# MCU.net
KiCad netlist of a schematic drawn in Altium Designer
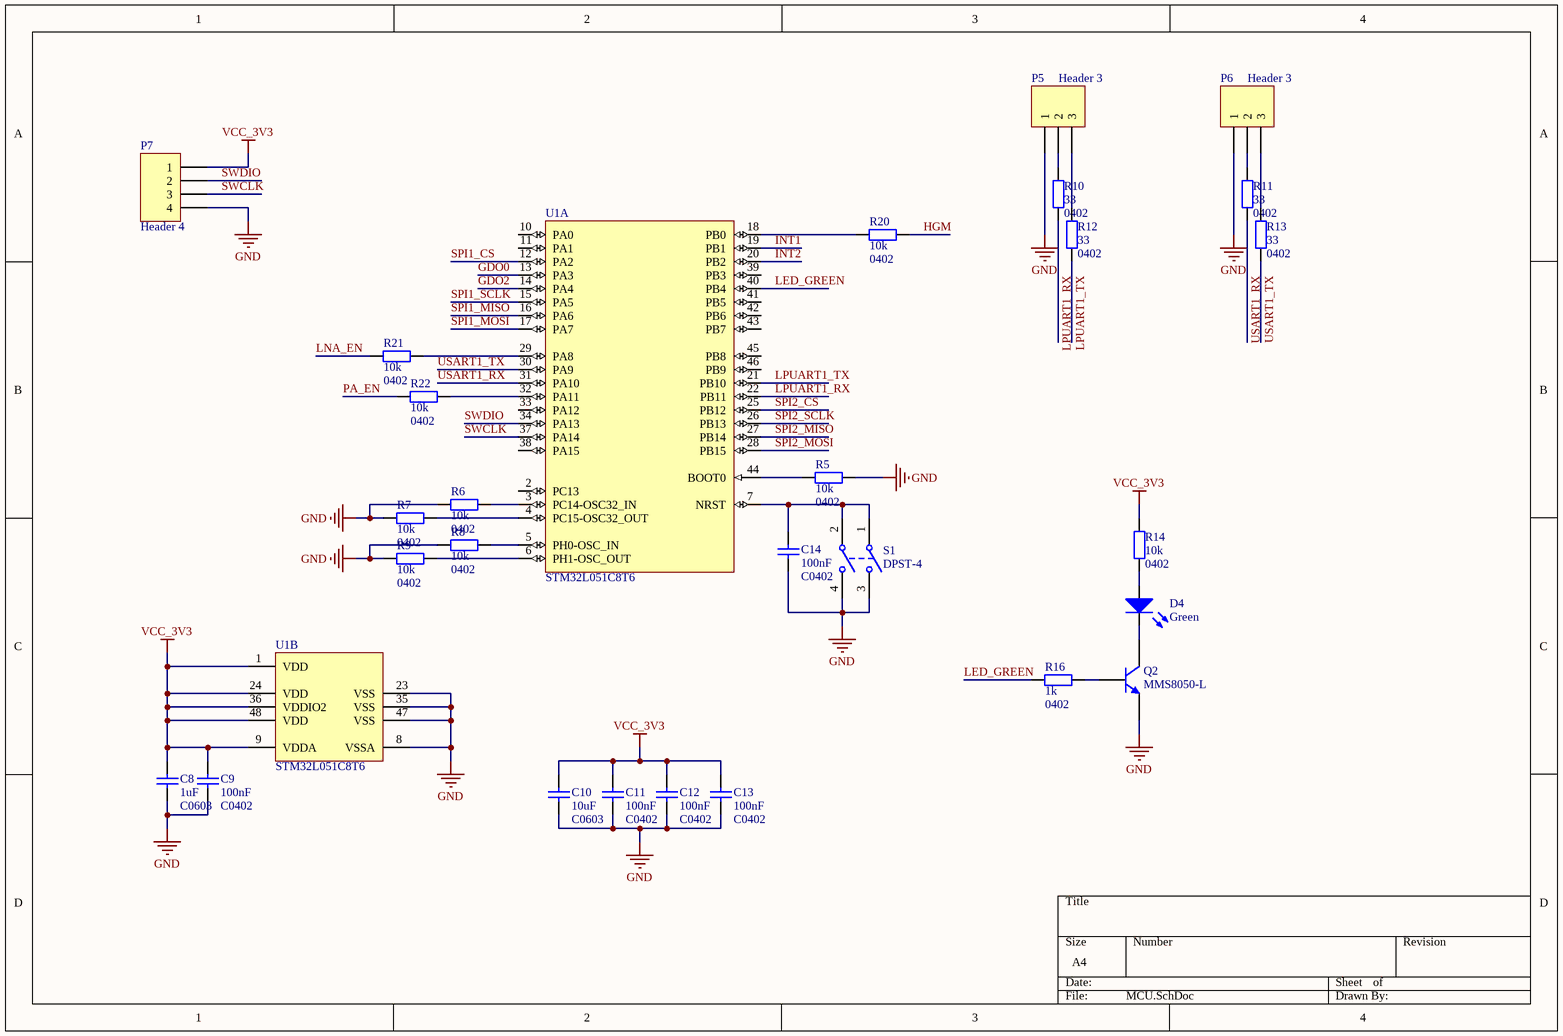
[diagram p0: MCU.SchDoc]

(export (version "E")
  (design (tool "Eeschema 10.0.6"))
  (components
    (comp (ref "C8")
      (value "1uF")
      (footprint "1608[0603]")
      (description "Capacitor (0603,X5R,1uF,DC 10V,+/-10%) TDK")
      (fields (field (name "PACKAGEREFERENCE") "C0603") (field (name "PUBLISHER") "Altium Limited"))
      (libsource (lib "RFID_CC1101PA2") (part "CGA3E2X5R1A105K080AA"))
    )
    (comp (ref "C9")
      (value "100nF")
      (footprint "0402")
      (description "Capacitor (0402,X5R,100nF,DC 10V,±10%) TDK")
      (fields (field (name "PACKAGEREFERENCE") "C0402") (field (name "PUBLISHER") "Altium Limited"))
      (libsource (lib "RFID_CC1101PA2") (part "CGA2B2X5R1A104K050BA"))
    )
    (comp (ref "C10")
      (value "10uF")
      (footprint "1608[0603]")
      (description "Capacitor (0603,X5R,10uF,DC 10V,±10%) TDK")
      (fields (field (name "PACKAGEREFERENCE") "C0603") (field (name "PUBLISHER") "Altium Limited"))
      (libsource (lib "RFID_CC1101PA2") (part "C1608X5R1A106K080AC"))
    )
    (comp (ref "C11")
      (value "100nF")
      (footprint "0402")
      (description "Capacitor (0402,X5R,100nF,DC 10V,±10%) TDK")
      (fields (field (name "PACKAGEREFERENCE") "C0402") (field (name "PUBLISHER") "Altium Limited"))
      (libsource (lib "RFID_CC1101PA2") (part "CGA2B2X5R1A104K050BA"))
    )
    (comp (ref "C12")
      (value "100nF")
      (footprint "0402")
      (description "Capacitor (0402,X5R,100nF,DC 10V,±10%) TDK")
      (fields (field (name "PACKAGEREFERENCE") "C0402") (field (name "PUBLISHER") "Altium Limited"))
      (libsource (lib "RFID_CC1101PA2") (part "CGA2B2X5R1A104K050BA"))
    )
    (comp (ref "C13")
      (value "100nF")
      (footprint "0402")
      (description "Capacitor (0402,X5R,100nF,DC 10V,±10%) TDK")
      (fields (field (name "PACKAGEREFERENCE") "C0402") (field (name "PUBLISHER") "Altium Limited"))
      (libsource (lib "RFID_CC1101PA2") (part "CGA2B2X5R1A104K050BA"))
    )
    (comp (ref "C14")
      (value "100nF")
      (footprint "0402")
      (description "Capacitor (0402,X5R,100nF,DC 10V,±10%) TDK")
      (fields (field (name "PACKAGEREFERENCE") "C0402") (field (name "PUBLISHER") "Altium Limited"))
      (libsource (lib "RFID_CC1101PA2") (part "CGA2B2X5R1A104K050BA"))
    )
    (comp (ref "D4")
      (value "Green")
      (footprint "0603/K")
      (description "Standard 0603 SMD LED, Green, 2.1V,-40 °C to +100 °C")
      (fields (field (name "PUBLISHER") "Altium Limited"))
      (libsource (lib "GPS_GPRS") (part "TLMG1100-GS08"))
    )
    (comp (ref "P5")
      (value "Header 3")
      (footprint "HDR1X3")
      (description "Header, 3-Pin")
      (fields (field (name "PUBLISHER") "Altium Limited"))
      (libsource (lib "GPS_NB") (part "Header 3"))
    )
    (comp (ref "P6")
      (value "Header 3")
      (footprint "HDR1X3")
      (description "Header, 3-Pin")
      (fields (field (name "PUBLISHER") "Altium Limited"))
      (libsource (lib "GPS_NB") (part "Header 3"))
    )
    (comp (ref "P7")
      (value "Header 4")
      (footprint "HDR1x4-2MM")
      (description "Header, 4-Pin")
      (fields (field (name "PUBLISHER") "Altium Limited"))
      (libsource (lib "TMR_Header") (part "Header 4"))
    )
    (comp (ref "Q2")
      (value "MMS8050-L")
      (footprint "SOT-23B_N")
      (description "NPN Silicon  Plastic-Encapsulate  Transistor , MCC , Range:120-200")
      (fields (field (name "PUBLISHER") "Altium Limited"))
      (libsource (lib "GPS_NB") (part "MMS8050-L"))
    )
    (comp (ref "R5")
      (value "10k")
      (footprint "RESC1005X04N")
      (description "Resistor 0402(1005) 10kΩ ±1%")
      (fields (field (name "PACKAGEREFERENCE") "0402"))
      (libsource (lib "RFID_CC1101PA2") (part "RC0402FR-0710KL"))
    )
    (comp (ref "R6")
      (value "10k")
      (footprint "RESC1005X04N")
      (description "Resistor 0402(1005) 10kΩ ±1%")
      (fields (field (name "PACKAGEREFERENCE") "0402"))
      (libsource (lib "RFID_CC1101PA2") (part "RC0402FR-0710KL"))
    )
    (comp (ref "R7")
      (value "10k")
      (footprint "RESC1005X04N")
      (description "Resistor 0402(1005) 10kΩ ±1%")
      (fields (field (name "PACKAGEREFERENCE") "0402"))
      (libsource (lib "RFID_CC1101PA2") (part "RC0402FR-0710KL"))
    )
    (comp (ref "R8")
      (value "10k")
      (footprint "RESC1005X04N")
      (description "Resistor 0402(1005) 10kΩ ±1%")
      (fields (field (name "PACKAGEREFERENCE") "0402"))
      (libsource (lib "RFID_CC1101PA2") (part "RC0402FR-0710KL"))
    )
    (comp (ref "R9")
      (value "10k")
      (footprint "RESC1005X04N")
      (description "Resistor 0402(1005) 10kΩ ±1%")
      (fields (field (name "PACKAGEREFERENCE") "0402"))
      (libsource (lib "RFID_CC1101PA2") (part "RC0402FR-0710KL"))
    )
    (comp (ref "R10")
      (value "33")
      (footprint "RESC1005X04N")
      (description "Resistor 0402(1005) 33Ω ±1%")
      (fields (field (name "PACKAGEREFERENCE") "0402"))
      (libsource (lib "GPS_NB") (part "RC0402FR-0733RL"))
    )
    (comp (ref "R11")
      (value "33")
      (footprint "RESC1005X04N")
      (description "Resistor 0402(1005) 33Ω ±1%")
      (fields (field (name "PACKAGEREFERENCE") "0402"))
      (libsource (lib "GPS_NB") (part "RC0402FR-0733RL"))
    )
    (comp (ref "R12")
      (value "33")
      (footprint "RESC1005X04N")
      (description "Resistor 0402(1005) 33Ω ±1%")
      (fields (field (name "PACKAGEREFERENCE") "0402"))
      (libsource (lib "") (part "RC0402FR-0733RL_1"))
    )
    (comp (ref "R13")
      (value "33")
      (footprint "RESC1005X04N")
      (description "Resistor 0402(1005) 33Ω ±1%")
      (fields (field (name "PACKAGEREFERENCE") "0402"))
      (libsource (lib "") (part "RC0402FR-0733RL_1"))
    )
    (comp (ref "R14")
      (value "10k")
      (footprint "RESC1005X04N")
      (description "Resistor 0402(1005) 10kΩ ±1%")
      (fields (field (name "PACKAGEREFERENCE") "0402"))
      (libsource (lib "GPS_NB") (part "RC0402FR-0710KL"))
    )
    (comp (ref "R16")
      (value "1k")
      (footprint "RESC1005X04N")
      (description "Resistor 0402(1005) 1kΩ ±1%")
      (fields (field (name "PACKAGEREFERENCE") "0402"))
      (libsource (lib "GPS_NB") (part "RC0402FR-071KL"))
    )
    (comp (ref "R20")
      (value "10k")
      (footprint "RESC1005X04N")
      (description "Resistor 0402(1005) 10kΩ ±1%")
      (fields (field (name "PACKAGEREFERENCE") "0402"))
      (libsource (lib "RFID_CC1101_869MHz") (part "RC0402FR-0710KL"))
    )
    (comp (ref "R21")
      (value "10k")
      (footprint "RESC1005X04N")
      (description "Resistor 0402(1005) 10kΩ ±1%")
      (fields (field (name "PACKAGEREFERENCE") "0402"))
      (libsource (lib "RFID_CC1101_869MHz") (part "RC0402FR-0710KL"))
    )
    (comp (ref "R22")
      (value "10k")
      (footprint "RESC1005X04N")
      (description "Resistor 0402(1005) 10kΩ ±1%")
      (fields (field (name "PACKAGEREFERENCE") "0402"))
      (libsource (lib "RFID_CC1101_869MHz") (part "RC0402FR-0710KL"))
    )
    (comp (ref "S1")
      (value "DPST-4")
      (footprint "DPST")
      (description "5.2*5.2轻触开关")
      (fields (field (name "PUBLISHER") "Altium Limited"))
      (libsource (lib "RFID_CC1101PA2") (part "CX-G001"))
    )
    (comp (ref "U1")
      (value "STM32L051C8T6")
      (footprint "STM-LQFP48_N")
      (libsource (lib "RFID_CC1101PA2") (part "STM32L051C8T6"))
    )
  )
  (nets
    (net (code "1") (name "/GDO0") (class "Default")
      (node (ref "U1") (pin "13") (pinfunction "PA3_13") (pintype "bidirectional"))
    )
    (net (code "2") (name "/GDO2") (class "Default")
      (node (ref "U1") (pin "14") (pinfunction "PA4_14") (pintype "bidirectional"))
    )
    (net (code "3") (name "/HGM") (class "Default")
      (node (ref "R20") (pin "2") (pinfunction "2_2") (pintype "passive"))
    )
    (net (code "4") (name "/INT1") (class "Default")
      (node (ref "U1") (pin "19") (pinfunction "PB1_19") (pintype "bidirectional"))
    )
    (net (code "5") (name "/INT2") (class "Default")
      (node (ref "U1") (pin "20") (pinfunction "PB2_20") (pintype "bidirectional"))
    )
    (net (code "6") (name "/LED_GREEN") (class "Default")
      (node (ref "R16") (pin "1") (pinfunction "1_1") (pintype "passive"))
      (node (ref "U1") (pin "40") (pinfunction "PB4_40") (pintype "bidirectional"))
    )
    (net (code "7") (name "/LNA_EN") (class "Default")
      (node (ref "R21") (pin "1") (pinfunction "1_1") (pintype "passive"))
    )
    (net (code "8") (name "/LPUART1_RX") (class "Default")
      (node (ref "R10") (pin "1") (pinfunction "1_1") (pintype "passive"))
      (node (ref "U1") (pin "22") (pinfunction "PB11_22") (pintype "bidirectional"))
    )
    (net (code "9") (name "/LPUART1_TX") (class "Default")
      (node (ref "R12") (pin "2") (pinfunction "2_2") (pintype "passive"))
      (node (ref "U1") (pin "21") (pinfunction "PB10_21") (pintype "bidirectional"))
    )
    (net (code "10") (name "/PA_EN") (class "Default")
      (node (ref "R22") (pin "1") (pinfunction "1_1") (pintype "passive"))
    )
    (net (code "11") (name "/SPI1_CS") (class "Default")
      (node (ref "U1") (pin "12") (pinfunction "PA2_12") (pintype "bidirectional"))
    )
    (net (code "12") (name "/SPI1_MISO") (class "Default")
      (node (ref "U1") (pin "16") (pinfunction "PA6_16") (pintype "bidirectional"))
    )
    (net (code "13") (name "/SPI1_MOSI") (class "Default")
      (node (ref "U1") (pin "17") (pinfunction "PA7_17") (pintype "bidirectional"))
    )
    (net (code "14") (name "/SPI1_SCLK") (class "Default")
      (node (ref "U1") (pin "15") (pinfunction "PA5_15") (pintype "bidirectional"))
    )
    (net (code "15") (name "/SPI2_CS") (class "Default")
      (node (ref "U1") (pin "25") (pinfunction "PB12_25") (pintype "bidirectional"))
    )
    (net (code "16") (name "/SPI2_MISO") (class "Default")
      (node (ref "U1") (pin "27") (pinfunction "PB14_27") (pintype "bidirectional"))
    )
    (net (code "17") (name "/SPI2_MOSI") (class "Default")
      (node (ref "U1") (pin "28") (pinfunction "PB15_28") (pintype "bidirectional"))
    )
    (net (code "18") (name "/SPI2_SCLK") (class "Default")
      (node (ref "U1") (pin "26") (pinfunction "PB13_26") (pintype "bidirectional"))
    )
    (net (code "19") (name "/SWCLK") (class "Default")
      (node (ref "P7") (pin "3") (pinfunction "3_3") (pintype "passive"))
      (node (ref "U1") (pin "37") (pinfunction "PA14_37") (pintype "bidirectional"))
    )
    (net (code "20") (name "/SWDIO") (class "Default")
      (node (ref "P7") (pin "2") (pinfunction "2_2") (pintype "passive"))
      (node (ref "U1") (pin "34") (pinfunction "PA13_34") (pintype "bidirectional"))
    )
    (net (code "21") (name "/USART1_RX") (class "Default")
      (node (ref "R11") (pin "1") (pinfunction "1_1") (pintype "passive"))
      (node (ref "U1") (pin "31") (pinfunction "PA10_31") (pintype "bidirectional"))
    )
    (net (code "22") (name "/USART1_TX") (class "Default")
      (node (ref "R13") (pin "2") (pinfunction "2_2") (pintype "passive"))
      (node (ref "U1") (pin "30") (pinfunction "PA9_30") (pintype "bidirectional"))
    )
    (net (code "23") (name "GND") (class "Default")
      (node (ref "C10") (pin "1") (pinfunction "1_1") (pintype "passive"))
      (node (ref "C11") (pin "2") (pinfunction "2_2") (pintype "passive"))
      (node (ref "C12") (pin "2") (pinfunction "2_2") (pintype "passive"))
      (node (ref "C13") (pin "2") (pinfunction "2_2") (pintype "passive"))
      (node (ref "C14") (pin "2") (pinfunction "2_2") (pintype "passive"))
      (node (ref "C8") (pin "1") (pinfunction "1_1") (pintype "passive"))
      (node (ref "C9") (pin "1") (pinfunction "1_1") (pintype "passive"))
      (node (ref "P5") (pin "1") (pinfunction "1_1") (pintype "passive"))
      (node (ref "P6") (pin "1") (pinfunction "1_1") (pintype "passive"))
      (node (ref "P7") (pin "4") (pinfunction "4_4") (pintype "passive"))
      (node (ref "Q2") (pin "E") (pinfunction "E_E") (pintype "passive"))
      (node (ref "R5") (pin "2") (pinfunction "2_2") (pintype "passive"))
      (node (ref "R6") (pin "1") (pinfunction "1_1") (pintype "passive"))
      (node (ref "R7") (pin "1") (pinfunction "1_1") (pintype "passive"))
      (node (ref "R8") (pin "1") (pinfunction "1_1") (pintype "passive"))
      (node (ref "R9") (pin "1") (pinfunction "1_1") (pintype "passive"))
      (node (ref "S1") (pin "3") (pinfunction "NO1_3") (pintype "passive"))
      (node (ref "S1") (pin "4") (pinfunction "NO2_4") (pintype "passive"))
      (node (ref "U1") (pin "23") (pinfunction "VSS_23") (pintype "power_in"))
      (node (ref "U1") (pin "35") (pinfunction "VSS_35") (pintype "power_in"))
      (node (ref "U1") (pin "47") (pinfunction "VSS_47") (pintype "power_in"))
      (node (ref "U1") (pin "8") (pinfunction "VSSA_8") (pintype "power_in"))
    )
    (net (code "24") (name "Net-(D4-PadA)") (class "Default")
      (node (ref "D4") (pin "A") (pinfunction "A_A") (pintype "passive"))
      (node (ref "R14") (pin "1") (pinfunction "1_1") (pintype "passive"))
    )
    (net (code "25") (name "Net-(D4-PadK)") (class "Default")
      (node (ref "D4") (pin "K") (pinfunction "K_K") (pintype "passive"))
      (node (ref "Q2") (pin "C") (pinfunction "C_C") (pintype "passive"))
    )
    (net (code "26") (name "Net-(P5-Pad2)") (class "Default")
      (node (ref "P5") (pin "2") (pinfunction "2_2") (pintype "passive"))
      (node (ref "R10") (pin "2") (pinfunction "2_2") (pintype "passive"))
    )
    (net (code "27") (name "Net-(P5-Pad3)") (class "Default")
      (node (ref "P5") (pin "3") (pinfunction "3_3") (pintype "passive"))
      (node (ref "R12") (pin "1") (pinfunction "1_1") (pintype "passive"))
    )
    (net (code "28") (name "Net-(P6-Pad2)") (class "Default")
      (node (ref "P6") (pin "2") (pinfunction "2_2") (pintype "passive"))
      (node (ref "R11") (pin "2") (pinfunction "2_2") (pintype "passive"))
    )
    (net (code "29") (name "Net-(P6-Pad3)") (class "Default")
      (node (ref "P6") (pin "3") (pinfunction "3_3") (pintype "passive"))
      (node (ref "R13") (pin "1") (pinfunction "1_1") (pintype "passive"))
    )
    (net (code "30") (name "Net-(Q2-PadB)") (class "Default")
      (node (ref "Q2") (pin "B") (pinfunction "B_B") (pintype "passive"))
      (node (ref "R16") (pin "2") (pinfunction "2_2") (pintype "passive"))
    )
    (net (code "31") (name "Net-(S1-COMMON1)") (class "Default")
      (node (ref "C14") (pin "1") (pinfunction "1_1") (pintype "passive"))
      (node (ref "S1") (pin "1") (pinfunction "COMMON1_1") (pintype "passive"))
      (node (ref "S1") (pin "2") (pinfunction "COMMON2_2") (pintype "passive"))
      (node (ref "U1") (pin "7") (pinfunction "NRST_7") (pintype "bidirectional"))
    )
    (net (code "32") (name "Net-(U1A-BOOT0)") (class "Default")
      (node (ref "R5") (pin "1") (pinfunction "1_1") (pintype "passive"))
      (node (ref "U1") (pin "44") (pinfunction "BOOT0_44") (pintype "input"))
    )
    (net (code "33") (name "Net-(U1A-PA8)") (class "Default")
      (node (ref "R21") (pin "2") (pinfunction "2_2") (pintype "passive"))
      (node (ref "U1") (pin "29") (pinfunction "PA8_29") (pintype "bidirectional"))
    )
    (net (code "34") (name "Net-(U1A-PA11)") (class "Default")
      (node (ref "R22") (pin "2") (pinfunction "2_2") (pintype "passive"))
      (node (ref "U1") (pin "32") (pinfunction "PA11_32") (pintype "bidirectional"))
    )
    (net (code "35") (name "Net-(U1A-PB0)") (class "Default")
      (node (ref "R20") (pin "1") (pinfunction "1_1") (pintype "passive"))
      (node (ref "U1") (pin "18") (pinfunction "PB0_18") (pintype "bidirectional"))
    )
    (net (code "36") (name "Net-(U1A-PC14-OSC32_IN)") (class "Default")
      (node (ref "R6") (pin "2") (pinfunction "2_2") (pintype "passive"))
      (node (ref "U1") (pin "3") (pinfunction "PC14-OSC32_IN_3") (pintype "bidirectional"))
    )
    (net (code "37") (name "Net-(U1A-PC15-OSC32_OUT)") (class "Default")
      (node (ref "R7") (pin "2") (pinfunction "2_2") (pintype "passive"))
      (node (ref "U1") (pin "4") (pinfunction "PC15-OSC32_OUT_4") (pintype "bidirectional"))
    )
    (net (code "38") (name "Net-(U1A-PH0-OSC_IN)") (class "Default")
      (node (ref "R8") (pin "2") (pinfunction "2_2") (pintype "passive"))
      (node (ref "U1") (pin "5") (pinfunction "PH0-OSC_IN_5") (pintype "bidirectional"))
    )
    (net (code "39") (name "Net-(U1A-PH1-OSC_OUT)") (class "Default")
      (node (ref "R9") (pin "2") (pinfunction "2_2") (pintype "passive"))
      (node (ref "U1") (pin "6") (pinfunction "PH1-OSC_OUT_6") (pintype "bidirectional"))
    )
    (net (code "40") (name "VCC_3V3") (class "Default")
      (node (ref "C10") (pin "2") (pinfunction "2_2") (pintype "passive"))
      (node (ref "C11") (pin "1") (pinfunction "1_1") (pintype "passive"))
      (node (ref "C12") (pin "1") (pinfunction "1_1") (pintype "passive"))
      (node (ref "C13") (pin "1") (pinfunction "1_1") (pintype "passive"))
      (node (ref "C8") (pin "2") (pinfunction "2_2") (pintype "passive"))
      (node (ref "C9") (pin "2") (pinfunction "2_2") (pintype "passive"))
      (node (ref "P7") (pin "1") (pinfunction "1_1") (pintype "passive"))
      (node (ref "R14") (pin "2") (pinfunction "2_2") (pintype "passive"))
      (node (ref "U1") (pin "1") (pinfunction "VDD_1") (pintype "power_in"))
      (node (ref "U1") (pin "24") (pinfunction "VDD_24") (pintype "power_in"))
      (node (ref "U1") (pin "36") (pinfunction "VDDIO2_36") (pintype "power_in"))
      (node (ref "U1") (pin "48") (pinfunction "VDD_48") (pintype "power_in"))
      (node (ref "U1") (pin "9") (pinfunction "VDDA_9") (pintype "power_in"))
    )
    (net (code "41") (name "unconnected-(U1A-PA0-Pad10)") (class "Default")
      (node (ref "U1") (pin "10") (pinfunction "PA0_10") (pintype "bidirectional"))
    )
    (net (code "42") (name "unconnected-(U1A-PA1-Pad11)") (class "Default")
      (node (ref "U1") (pin "11") (pinfunction "PA1_11") (pintype "bidirectional"))
    )
    (net (code "43") (name "unconnected-(U1A-PA12-Pad33)") (class "Default")
      (node (ref "U1") (pin "33") (pinfunction "PA12_33") (pintype "bidirectional"))
    )
    (net (code "44") (name "unconnected-(U1A-PA15-Pad38)") (class "Default")
      (node (ref "U1") (pin "38") (pinfunction "PA15_38") (pintype "bidirectional"))
    )
    (net (code "45") (name "unconnected-(U1A-PB3-Pad39)") (class "Default")
      (node (ref "U1") (pin "39") (pinfunction "PB3_39") (pintype "bidirectional"))
    )
    (net (code "46") (name "unconnected-(U1A-PB5-Pad41)") (class "Default")
      (node (ref "U1") (pin "41") (pinfunction "PB5_41") (pintype "bidirectional"))
    )
    (net (code "47") (name "unconnected-(U1A-PB6-Pad42)") (class "Default")
      (node (ref "U1") (pin "42") (pinfunction "PB6_42") (pintype "bidirectional"))
    )
    (net (code "48") (name "unconnected-(U1A-PB7-Pad43)") (class "Default")
      (node (ref "U1") (pin "43") (pinfunction "PB7_43") (pintype "bidirectional"))
    )
    (net (code "49") (name "unconnected-(U1A-PB8-Pad45)") (class "Default")
      (node (ref "U1") (pin "45") (pinfunction "PB8_45") (pintype "bidirectional"))
    )
    (net (code "50") (name "unconnected-(U1A-PB9-Pad46)") (class "Default")
      (node (ref "U1") (pin "46") (pinfunction "PB9_46") (pintype "bidirectional"))
    )
    (net (code "51") (name "unconnected-(U1A-PC13-Pad2)") (class "Default")
      (node (ref "U1") (pin "2") (pinfunction "PC13_2") (pintype "bidirectional"))
    )
  )
)
